# VL53L0x.net
KiCad netlist of a schematic drawn in Altium Designer
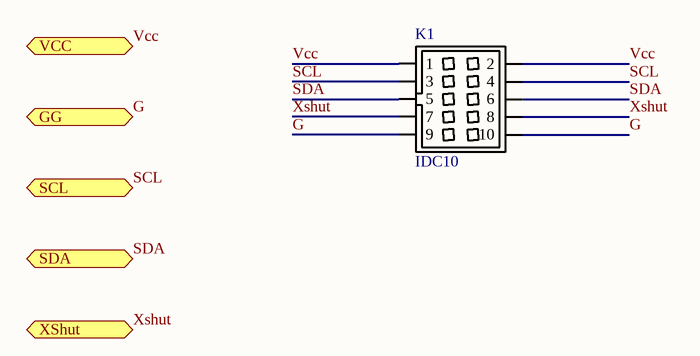
[diagram p0: VL53L0x.SchDoc]

(export (version "E")
  (design (tool "Eeschema 10.0.6"))
  (components
    (comp (ref "K1")
      (value "IDC10")
      (footprint "IDC10-B")
      (description "BOXHEADER 10 PIN")
      (fields
        (field (name "MANUFACTURER") "Assmann Electronics Inc")
        (field (name "MANUFACTURER PART NUMBER") "AWHW10G-0202-T-R")
      )
      (libsource (lib "vh_altium_library") (part "IDC10"))
    )
  )
  (nets
    (net (code "1") (name "/G") (class "Default")
      (node (ref "K1") (pin "10") (pinfunction "10_10") (pintype "passive"))
      (node (ref "K1") (pin "9") (pinfunction "9_9") (pintype "passive"))
    )
    (net (code "2") (name "/SCL") (class "Default")
      (node (ref "K1") (pin "3") (pinfunction "3_3") (pintype "passive"))
      (node (ref "K1") (pin "4") (pinfunction "4_4") (pintype "passive"))
    )
    (net (code "3") (name "/SDA") (class "Default")
      (node (ref "K1") (pin "5") (pinfunction "5_5") (pintype "passive"))
      (node (ref "K1") (pin "6") (pinfunction "6_6") (pintype "passive"))
    )
    (net (code "4") (name "/Vcc") (class "Default")
      (node (ref "K1") (pin "1") (pinfunction "1_1") (pintype "passive"))
      (node (ref "K1") (pin "2") (pinfunction "2_2") (pintype "passive"))
    )
    (net (code "5") (name "/Xshut") (class "Default")
      (node (ref "K1") (pin "7") (pinfunction "7_7") (pintype "passive"))
      (node (ref "K1") (pin "8") (pinfunction "8_8") (pintype "passive"))
    )
  )
)
